# lm3410-sepic-led-driver-test-pcb.net
KiCad netlist of a schematic drawn in EAGLE
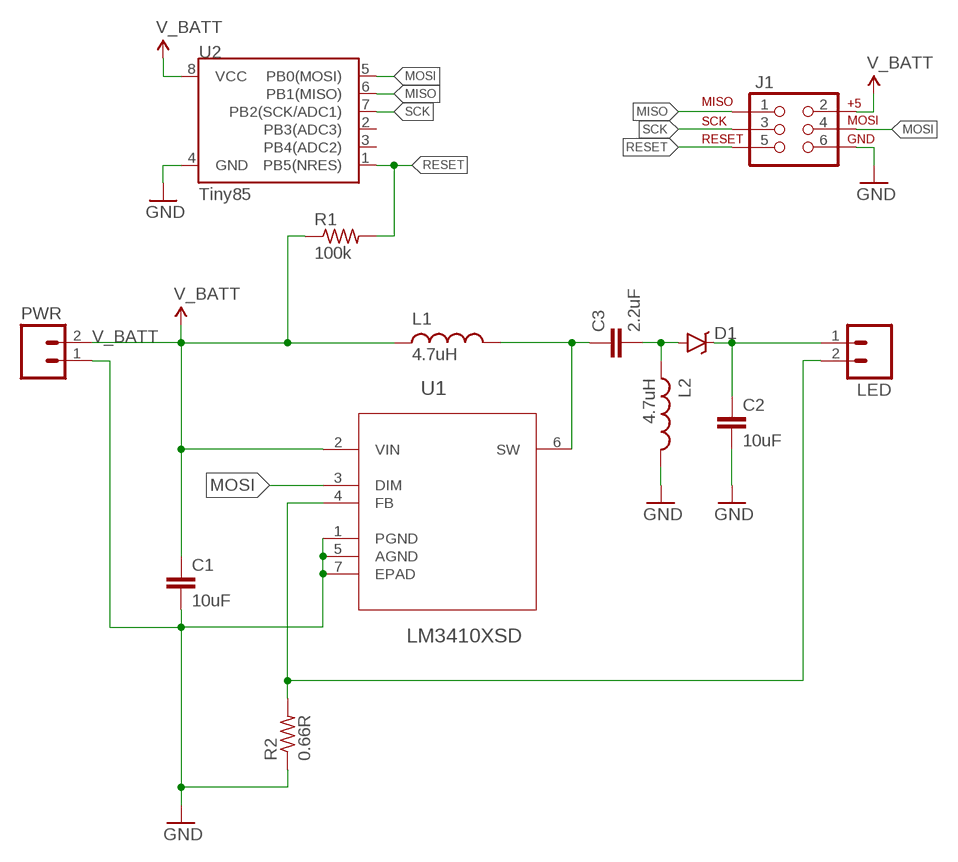
[diagram p0: schematic, sheet 1]

(export (version "E")
  (design (tool "Eeschema 10.0.6"))
  (components
    (comp (ref "C1")
      (value "10uF")
      (footprint "eagle-import:C0805")
      (libsource (lib "eagle-import") (part "CAPACITOR-CERAMICC0805"))
    )
    (comp (ref "C2")
      (value "10uF")
      (footprint "eagle-import:C0805")
      (libsource (lib "eagle-import") (part "CAPACITOR-CERAMICC0805"))
    )
    (comp (ref "C3")
      (value "2.2uF")
      (footprint "eagle-import:C0805")
      (libsource (lib "eagle-import") (part "CAPACITOR-CERAMICC0805"))
    )
    (comp (ref "D1")
      (value "BAT20J")
      (footprint "eagle-import:SOD-323")
      (libsource (lib "eagle-import") (part "DIODE-SCHOTTKYBAT20J"))
    )
    (comp (ref "J1")
      (value "AVR_SPI_PRG_6PTH")
      (footprint "eagle-import:2X3")
      (libsource (lib "eagle-import") (part "AVR_SPI_PRG_6PTH"))
    )
    (comp (ref "L1")
      (value "4.7uH")
      (footprint "eagle-import:INDUCTOR_2X1.6MM")
      (libsource (lib "eagle-import") (part "INDUCTORIFSC-0806"))
    )
    (comp (ref "L2")
      (value "4.7uH")
      (footprint "eagle-import:INDUCTOR_2X1.6MM")
      (libsource (lib "eagle-import") (part "INDUCTORIFSC-0806"))
    )
    (comp (ref "LED")
      (value "M02PTH")
      (footprint "eagle-import:1X02")
      (libsource (lib "eagle-import") (part "M02PTH"))
    )
    (comp (ref "PWR")
      (value "M02PTH")
      (footprint "eagle-import:1X02")
      (libsource (lib "eagle-import") (part "M02PTH"))
    )
    (comp (ref "R1")
      (value "100k")
      (footprint "eagle-import:R0603")
      (libsource (lib "eagle-import") (part "RESISTORR0603"))
    )
    (comp (ref "R2")
      (value "0.66R")
      (footprint "eagle-import:R1206")
      (libsource (lib "eagle-import") (part "RESISTORR1206"))
    )
    (comp (ref "U1")
      (value "LM3410XSD")
      (footprint "eagle-import:DFN300X300X80-7N")
      (libsource (lib "eagle-import") (part "LM3410XSD"))
    )
    (comp (ref "U2")
      (value "Tiny85")
      (footprint "eagle-import:SO08-EIAJ")
      (libsource (lib "eagle-import") (part "ATTINY45TINY85-20-SMT"))
    )
  )
  (nets
    (net (code "1") (name "GND") (class "Default")
      (node (ref "C1") (pin "2") (pinfunction "2_2") (pintype "passive"))
      (node (ref "C2") (pin "2") (pinfunction "2_2") (pintype "passive"))
      (node (ref "J1") (pin "6") (pinfunction "6_6") (pintype "passive"))
      (node (ref "L2") (pin "P$2") (pinfunction "2_P$2") (pintype "passive"))
      (node (ref "PWR") (pin "1") (pinfunction "1_1") (pintype "passive"))
      (node (ref "R2") (pin "1") (pinfunction "1_1") (pintype "passive"))
      (node (ref "U1") (pin "1") (pinfunction "PGND_1") (pintype "passive"))
      (node (ref "U1") (pin "5") (pinfunction "AGND_5") (pintype "passive"))
      (node (ref "U1") (pin "7") (pinfunction "EPAD_7") (pintype "passive"))
      (node (ref "U2") (pin "4") (pinfunction "GND_4") (pintype "bidirectional"))
    )
    (net (code "2") (name "MISO") (class "Default")
      (node (ref "J1") (pin "1") (pinfunction "1_1") (pintype "passive"))
      (node (ref "U2") (pin "6") (pinfunction "PB1(MISO)_6") (pintype "bidirectional"))
    )
    (net (code "3") (name "MOSI") (class "Default")
      (node (ref "J1") (pin "4") (pinfunction "4_4") (pintype "passive"))
      (node (ref "U1") (pin "3") (pinfunction "DIM_3") (pintype "input"))
      (node (ref "U2") (pin "5") (pinfunction "PB0(MOSI)_5") (pintype "bidirectional"))
    )
    (net (code "4") (name "Net-(C2-Pad1)") (class "Default")
      (node (ref "C2") (pin "1") (pinfunction "1_1") (pintype "passive"))
      (node (ref "D1") (pin "C") (pinfunction "C_C") (pintype "passive"))
      (node (ref "LED") (pin "1") (pinfunction "1_1") (pintype "passive"))
    )
    (net (code "5") (name "Net-(L1-2)") (class "Default")
      (node (ref "C3") (pin "1") (pinfunction "1_1") (pintype "passive"))
      (node (ref "L1") (pin "P$2") (pinfunction "2_P$2") (pintype "passive"))
      (node (ref "U1") (pin "6") (pinfunction "SW_6") (pintype "output"))
    )
    (net (code "6") (name "Net-(L2-1)") (class "Default")
      (node (ref "C3") (pin "2") (pinfunction "2_2") (pintype "passive"))
      (node (ref "D1") (pin "A") (pinfunction "A_A") (pintype "passive"))
      (node (ref "L2") (pin "P$1") (pinfunction "1_P$1") (pintype "passive"))
    )
    (net (code "7") (name "Net-(U1-FB)") (class "Default")
      (node (ref "LED") (pin "2") (pinfunction "2_2") (pintype "passive"))
      (node (ref "R2") (pin "2") (pinfunction "2_2") (pintype "passive"))
      (node (ref "U1") (pin "4") (pinfunction "FB_4") (pintype "input"))
    )
    (net (code "8") (name "RESET") (class "Default")
      (node (ref "J1") (pin "5") (pinfunction "5_5") (pintype "passive"))
      (node (ref "R1") (pin "2") (pinfunction "2_2") (pintype "passive"))
      (node (ref "U2") (pin "1") (pinfunction "PB5(NRES)_1") (pintype "bidirectional"))
    )
    (net (code "9") (name "SCK") (class "Default")
      (node (ref "J1") (pin "3") (pinfunction "3_3") (pintype "passive"))
      (node (ref "U2") (pin "7") (pinfunction "PB2(SCK/ADC1)_7") (pintype "bidirectional"))
    )
    (net (code "10") (name "V_BATT") (class "Default")
      (node (ref "C1") (pin "1") (pinfunction "1_1") (pintype "passive"))
      (node (ref "J1") (pin "2") (pinfunction "2_2") (pintype "passive"))
      (node (ref "L1") (pin "P$1") (pinfunction "1_P$1") (pintype "passive"))
      (node (ref "PWR") (pin "2") (pinfunction "2_2") (pintype "passive"))
      (node (ref "R1") (pin "1") (pinfunction "1_1") (pintype "passive"))
      (node (ref "U1") (pin "2") (pinfunction "VIN_2") (pintype "power_in"))
      (node (ref "U2") (pin "8") (pinfunction "VCC_8") (pintype "bidirectional"))
    )
    (net (code "11") (name "unconnected-(U2-PB3(ADC3)-Pad2)") (class "Default")
      (node (ref "U2") (pin "2") (pinfunction "PB3(ADC3)_2") (pintype "bidirectional"))
    )
    (net (code "12") (name "unconnected-(U2-PB4(ADC2)-Pad3)") (class "Default")
      (node (ref "U2") (pin "3") (pinfunction "PB4(ADC2)_3") (pintype "bidirectional"))
    )
  )
)
